# adapter.net
KiCad netlist of a schematic drawn in EAGLE
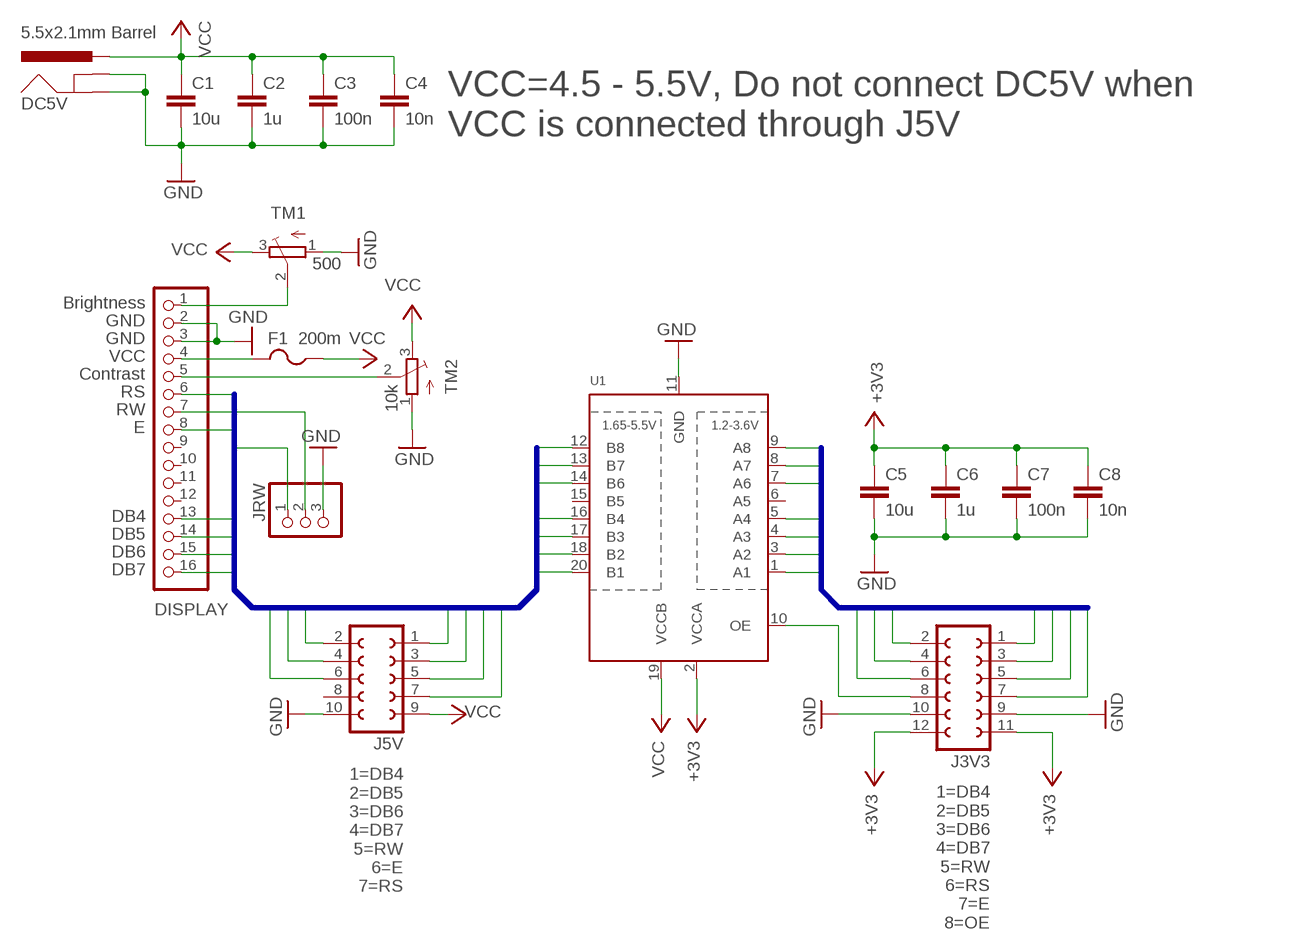
[diagram p0: schematic, sheet 1]

(export (version "E")
  (design (tool "Eeschema 10.0.6"))
  (components
    (comp (ref "C1")
      (value "10u")
      (footprint "eagle-import:C0603")
      (libsource (lib "eagle-import") (part "C-EUC0603"))
    )
    (comp (ref "C2")
      (value "1u")
      (footprint "eagle-import:C0603")
      (libsource (lib "eagle-import") (part "C-EUC0603"))
    )
    (comp (ref "C3")
      (value "100n")
      (footprint "eagle-import:C0603")
      (libsource (lib "eagle-import") (part "C-EUC0603"))
    )
    (comp (ref "C4")
      (value "10n")
      (footprint "eagle-import:C0603")
      (libsource (lib "eagle-import") (part "C-EUC0603"))
    )
    (comp (ref "C5")
      (value "10u")
      (footprint "eagle-import:C0603")
      (libsource (lib "eagle-import") (part "C-EUC0603"))
    )
    (comp (ref "C6")
      (value "1u")
      (footprint "eagle-import:C0603")
      (libsource (lib "eagle-import") (part "C-EUC0603"))
    )
    (comp (ref "C7")
      (value "100n")
      (footprint "eagle-import:C0603")
      (libsource (lib "eagle-import") (part "C-EUC0603"))
    )
    (comp (ref "C8")
      (value "10n")
      (footprint "eagle-import:C0603")
      (libsource (lib "eagle-import") (part "C-EUC0603"))
    )
    (comp (ref "DC5V")
      (value "5.5x2.1mm Barrel")
      (footprint "eagle-import:POWER_JACK_SMD")
      (libsource (lib "eagle-import") (part "POWER_JACKSMD"))
    )
    (comp (ref "DISPLAY")
      (value "PINHD-1X16")
      (footprint "eagle-import:1X16")
      (libsource (lib "eagle-import") (part "PINHD-1X16"))
    )
    (comp (ref "F1")
      (value "200m")
      (footprint "eagle-import:R1206")
      (libsource (lib "eagle-import") (part "PTCFUSE-1206"))
    )
    (comp (ref "J3V3")
      (value "FE06-2W")
      (footprint "eagle-import:FE06-2W")
      (libsource (lib "eagle-import") (part "FE06-2W"))
    )
    (comp (ref "J5V")
      (value "FE05-2W")
      (footprint "eagle-import:FE05-2W")
      (libsource (lib "eagle-import") (part "FE05-2W"))
    )
    (comp (ref "JRW")
      (value "PINHD-1X3/90")
      (footprint "eagle-import:1X03_90")
      (libsource (lib "eagle-import") (part "PINHD-1X3/90"))
    )
    (comp (ref "TM1")
      (value "500")
      (footprint "eagle-import:TC33X")
      (libsource (lib "eagle-import") (part "TRIMPOTTC33X"))
    )
    (comp (ref "TM2")
      (value "10k")
      (footprint "eagle-import:TC33X")
      (libsource (lib "eagle-import") (part "TRIMPOTTC33X"))
    )
    (comp (ref "U1")
      (value "TXB0108PWR")
      (footprint "eagle-import:TSSOP20")
      (libsource (lib "eagle-import") (part "TXB0108PWR"))
    )
  )
  (nets
    (net (code "1") (name "+3V3") (class "Default")
      (node (ref "C5") (pin "1") (pinfunction "1_1") (pintype "passive"))
      (node (ref "C6") (pin "1") (pinfunction "1_1") (pintype "passive"))
      (node (ref "C7") (pin "1") (pinfunction "1_1") (pintype "passive"))
      (node (ref "C8") (pin "1") (pinfunction "1_1") (pintype "passive"))
      (node (ref "J3V3") (pin "11") (pinfunction "11_11") (pintype "passive"))
      (node (ref "J3V3") (pin "12") (pinfunction "12_12") (pintype "passive"))
      (node (ref "U1") (pin "2") (pinfunction "VCCA_2") (pintype "bidirectional"))
    )
    (net (code "2") (name "/3DB4") (class "Default")
      (node (ref "J3V3") (pin "1") (pinfunction "1_1") (pintype "passive"))
      (node (ref "U1") (pin "1") (pinfunction "A1_1") (pintype "bidirectional"))
    )
    (net (code "3") (name "/3DB5") (class "Default")
      (node (ref "J3V3") (pin "2") (pinfunction "2_2") (pintype "passive"))
      (node (ref "U1") (pin "3") (pinfunction "A2_3") (pintype "bidirectional"))
    )
    (net (code "4") (name "/3DB6") (class "Default")
      (node (ref "J3V3") (pin "3") (pinfunction "3_3") (pintype "passive"))
      (node (ref "U1") (pin "4") (pinfunction "A3_4") (pintype "bidirectional"))
    )
    (net (code "5") (name "/3DB7") (class "Default")
      (node (ref "J3V3") (pin "4") (pinfunction "4_4") (pintype "passive"))
      (node (ref "U1") (pin "5") (pinfunction "A4_5") (pintype "bidirectional"))
    )
    (net (code "6") (name "/3E") (class "Default")
      (node (ref "J3V3") (pin "7") (pinfunction "7_7") (pintype "passive"))
      (node (ref "U1") (pin "9") (pinfunction "A8_9") (pintype "bidirectional"))
    )
    (net (code "7") (name "/3RS") (class "Default")
      (node (ref "J3V3") (pin "6") (pinfunction "6_6") (pintype "passive"))
      (node (ref "U1") (pin "8") (pinfunction "A7_8") (pintype "bidirectional"))
    )
    (net (code "8") (name "/3RW") (class "Default")
      (node (ref "J3V3") (pin "5") (pinfunction "5_5") (pintype "passive"))
      (node (ref "U1") (pin "7") (pinfunction "A6_7") (pintype "bidirectional"))
    )
    (net (code "9") (name "/DB4") (class "Default")
      (node (ref "DISPLAY") (pin "13") (pinfunction "13_13") (pintype "passive"))
      (node (ref "J5V") (pin "1") (pinfunction "1_1") (pintype "passive"))
      (node (ref "U1") (pin "20") (pinfunction "B1_20") (pintype "bidirectional"))
    )
    (net (code "10") (name "/DB5") (class "Default")
      (node (ref "DISPLAY") (pin "14") (pinfunction "14_14") (pintype "passive"))
      (node (ref "J5V") (pin "2") (pinfunction "2_2") (pintype "passive"))
      (node (ref "U1") (pin "18") (pinfunction "B2_18") (pintype "bidirectional"))
    )
    (net (code "11") (name "/DB6") (class "Default")
      (node (ref "DISPLAY") (pin "15") (pinfunction "15_15") (pintype "passive"))
      (node (ref "J5V") (pin "3") (pinfunction "3_3") (pintype "passive"))
      (node (ref "U1") (pin "17") (pinfunction "B3_17") (pintype "bidirectional"))
    )
    (net (code "12") (name "/DB7") (class "Default")
      (node (ref "DISPLAY") (pin "16") (pinfunction "16_16") (pintype "passive"))
      (node (ref "J5V") (pin "4") (pinfunction "4_4") (pintype "passive"))
      (node (ref "U1") (pin "16") (pinfunction "B4_16") (pintype "bidirectional"))
    )
    (net (code "13") (name "/E") (class "Default")
      (node (ref "DISPLAY") (pin "8") (pinfunction "8_8") (pintype "passive"))
      (node (ref "J5V") (pin "6") (pinfunction "6_6") (pintype "passive"))
      (node (ref "U1") (pin "12") (pinfunction "B8_12") (pintype "bidirectional"))
    )
    (net (code "14") (name "/RS") (class "Default")
      (node (ref "DISPLAY") (pin "6") (pinfunction "6_6") (pintype "passive"))
      (node (ref "J5V") (pin "7") (pinfunction "7_7") (pintype "passive"))
      (node (ref "U1") (pin "13") (pinfunction "B7_13") (pintype "bidirectional"))
    )
    (net (code "15") (name "/RW") (class "Default")
      (node (ref "J5V") (pin "5") (pinfunction "5_5") (pintype "passive"))
      (node (ref "JRW") (pin "1") (pinfunction "1_1") (pintype "passive"))
      (node (ref "U1") (pin "14") (pinfunction "B6_14") (pintype "bidirectional"))
    )
    (net (code "16") (name "GND") (class "Default")
      (node (ref "C1") (pin "2") (pinfunction "2_2") (pintype "passive"))
      (node (ref "C2") (pin "2") (pinfunction "2_2") (pintype "passive"))
      (node (ref "C3") (pin "2") (pinfunction "2_2") (pintype "passive"))
      (node (ref "C4") (pin "2") (pinfunction "2_2") (pintype "passive"))
      (node (ref "C5") (pin "2") (pinfunction "2_2") (pintype "passive"))
      (node (ref "C6") (pin "2") (pinfunction "2_2") (pintype "passive"))
      (node (ref "C7") (pin "2") (pinfunction "2_2") (pintype "passive"))
      (node (ref "C8") (pin "2") (pinfunction "2_2") (pintype "passive"))
      (node (ref "DC5V") (pin "GND") (pinfunction "GNDBREAK_GND") (pintype "bidirectional"))
      (node (ref "DC5V") (pin "P$4") (pinfunction "GND_P$4") (pintype "bidirectional"))
      (node (ref "DISPLAY") (pin "2") (pinfunction "2_2") (pintype "passive"))
      (node (ref "DISPLAY") (pin "3") (pinfunction "3_3") (pintype "passive"))
      (node (ref "J3V3") (pin "10") (pinfunction "10_10") (pintype "passive"))
      (node (ref "J3V3") (pin "9") (pinfunction "9_9") (pintype "passive"))
      (node (ref "J5V") (pin "10") (pinfunction "10_10") (pintype "passive"))
      (node (ref "JRW") (pin "3") (pinfunction "3_3") (pintype "passive"))
      (node (ref "TM1") (pin "1") (pinfunction "A_1") (pintype "passive"))
      (node (ref "TM2") (pin "1") (pinfunction "A_1") (pintype "passive"))
      (node (ref "U1") (pin "11") (pinfunction "GND_11") (pintype "bidirectional"))
    )
    (net (code "17") (name "Net-(DISPLAY-Pad4)") (class "Default")
      (node (ref "DISPLAY") (pin "4") (pinfunction "4_4") (pintype "passive"))
      (node (ref "F1") (pin "2") (pinfunction "2_2") (pintype "passive"))
    )
    (net (code "18") (name "Net-(DISPLAY-Pad7)") (class "Default")
      (node (ref "DISPLAY") (pin "7") (pinfunction "7_7") (pintype "passive"))
      (node (ref "JRW") (pin "2") (pinfunction "2_2") (pintype "passive"))
    )
    (net (code "19") (name "Net-(TM1-S)") (class "Default")
      (node (ref "DISPLAY") (pin "1") (pinfunction "1_1") (pintype "passive"))
      (node (ref "TM1") (pin "2") (pinfunction "S_2") (pintype "passive"))
    )
    (net (code "20") (name "Net-(TM2-S)") (class "Default")
      (node (ref "DISPLAY") (pin "5") (pinfunction "5_5") (pintype "passive"))
      (node (ref "TM2") (pin "2") (pinfunction "S_2") (pintype "passive"))
    )
    (net (code "21") (name "Net-(U1-OE)") (class "Default")
      (node (ref "J3V3") (pin "8") (pinfunction "8_8") (pintype "passive"))
      (node (ref "U1") (pin "10") (pinfunction "OE_10") (pintype "bidirectional"))
    )
    (net (code "22") (name "VCC") (class "Default")
      (node (ref "C1") (pin "1") (pinfunction "1_1") (pintype "passive"))
      (node (ref "C2") (pin "1") (pinfunction "1_1") (pintype "passive"))
      (node (ref "C3") (pin "1") (pinfunction "1_1") (pintype "passive"))
      (node (ref "C4") (pin "1") (pinfunction "1_1") (pintype "passive"))
      (node (ref "DC5V") (pin "VIN0") (pinfunction "PWR_VIN0") (pintype "bidirectional"))
      (node (ref "F1") (pin "1") (pinfunction "1_1") (pintype "passive"))
      (node (ref "J5V") (pin "9") (pinfunction "9_9") (pintype "passive"))
      (node (ref "TM1") (pin "3") (pinfunction "E_3") (pintype "passive"))
      (node (ref "TM2") (pin "3") (pinfunction "E_3") (pintype "passive"))
      (node (ref "U1") (pin "19") (pinfunction "VCCB_19") (pintype "bidirectional"))
    )
    (net (code "23") (name "unconnected-(DISPLAY-Pad9)") (class "Default")
      (node (ref "DISPLAY") (pin "9") (pinfunction "9_9") (pintype "passive"))
    )
    (net (code "24") (name "unconnected-(DISPLAY-Pad10)") (class "Default")
      (node (ref "DISPLAY") (pin "10") (pinfunction "10_10") (pintype "passive"))
    )
    (net (code "25") (name "unconnected-(DISPLAY-Pad11)") (class "Default")
      (node (ref "DISPLAY") (pin "11") (pinfunction "11_11") (pintype "passive"))
    )
    (net (code "26") (name "unconnected-(DISPLAY-Pad12)") (class "Default")
      (node (ref "DISPLAY") (pin "12") (pinfunction "12_12") (pintype "passive"))
    )
    (net (code "27") (name "unconnected-(J5V-Pad8)") (class "Default")
      (node (ref "J5V") (pin "8") (pinfunction "8_8") (pintype "passive"))
    )
    (net (code "28") (name "unconnected-(U1-A5-Pad6)") (class "Default")
      (node (ref "U1") (pin "6") (pinfunction "A5_6") (pintype "bidirectional"))
    )
    (net (code "29") (name "unconnected-(U1-B5-Pad15)") (class "Default")
      (node (ref "U1") (pin "15") (pinfunction "B5_15") (pintype "bidirectional"))
    )
  )
)
